# v1.net
KiCad netlist of a schematic drawn in EAGLE
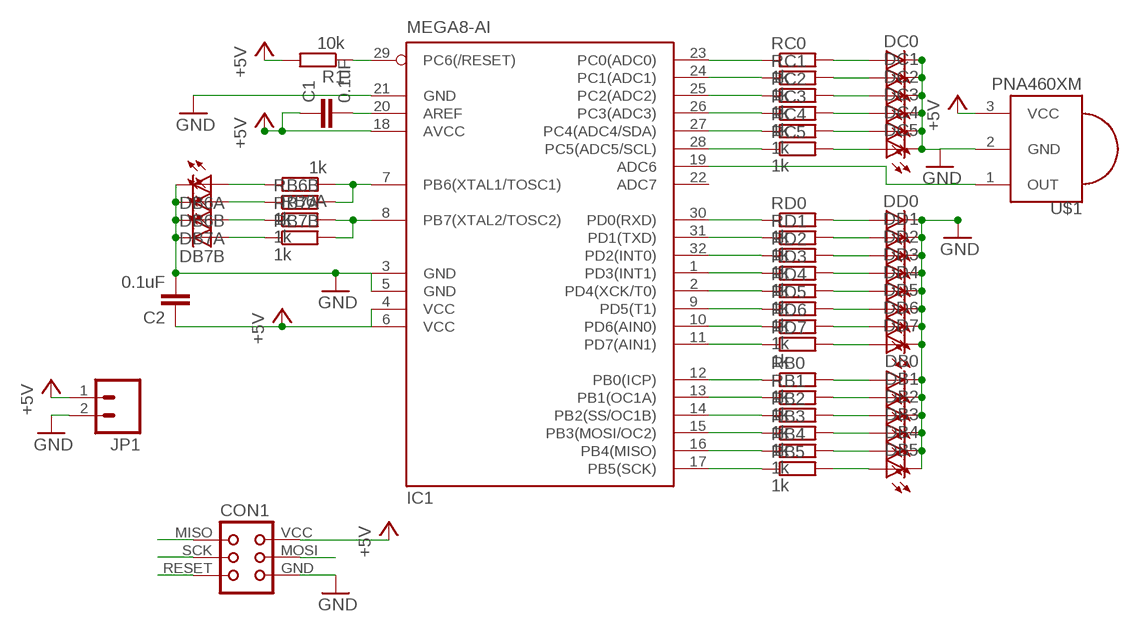
[diagram p0: schematic, sheet 1]

(export (version "E")
  (design (tool "Eeschema 10.0.6"))
  (components
    (comp (ref "C1")
      (value "0.1uF")
      (footprint "eagle-import:C1206")
      (libsource (lib "eagle-import") (part "C-EUC1206"))
    )
    (comp (ref "C2")
      (value "0.1uF")
      (footprint "eagle-import:C1206")
      (libsource (lib "eagle-import") (part "C-EUC1206"))
    )
    (comp (ref "CON1")
      (value "TINYISP")
      (footprint "eagle-import:TINYISP")
      (libsource (lib "eagle-import") (part "TINYISP"))
    )
    (comp (ref "DB0")
      (value "LED3MM")
      (footprint "eagle-import:LED3MM")
      (libsource (lib "eagle-import") (part "LED3MM"))
    )
    (comp (ref "DB1")
      (value "LED3MM")
      (footprint "eagle-import:LED3MM")
      (libsource (lib "eagle-import") (part "LED3MM"))
    )
    (comp (ref "DB2")
      (value "LED3MM")
      (footprint "eagle-import:LED3MM")
      (libsource (lib "eagle-import") (part "LED3MM"))
    )
    (comp (ref "DB3")
      (value "LED3MM")
      (footprint "eagle-import:LED3MM")
      (libsource (lib "eagle-import") (part "LED3MM"))
    )
    (comp (ref "DB4")
      (value "LED3MM")
      (footprint "eagle-import:LED3MM")
      (libsource (lib "eagle-import") (part "LED3MM"))
    )
    (comp (ref "DB5")
      (value "LED3MM")
      (footprint "eagle-import:LED3MM")
      (libsource (lib "eagle-import") (part "LED3MM"))
    )
    (comp (ref "DB6A")
      (value "LED3MM")
      (footprint "eagle-import:LED3MM")
      (libsource (lib "eagle-import") (part "LED3MM"))
    )
    (comp (ref "DB6B")
      (value "LED3MM")
      (footprint "eagle-import:LED3MM")
      (libsource (lib "eagle-import") (part "LED3MM"))
    )
    (comp (ref "DB7A")
      (value "LED3MM")
      (footprint "eagle-import:LED3MM")
      (libsource (lib "eagle-import") (part "LED3MM"))
    )
    (comp (ref "DB7B")
      (value "LED3MM")
      (footprint "eagle-import:LED3MM")
      (libsource (lib "eagle-import") (part "LED3MM"))
    )
    (comp (ref "DC0")
      (value "LED3MM")
      (footprint "eagle-import:LED3MM")
      (libsource (lib "eagle-import") (part "LED3MM"))
    )
    (comp (ref "DC1")
      (value "LED3MM")
      (footprint "eagle-import:LED3MM")
      (libsource (lib "eagle-import") (part "LED3MM"))
    )
    (comp (ref "DC2")
      (value "LED3MM")
      (footprint "eagle-import:LED3MM")
      (libsource (lib "eagle-import") (part "LED3MM"))
    )
    (comp (ref "DC3")
      (value "LED3MM")
      (footprint "eagle-import:LED3MM")
      (libsource (lib "eagle-import") (part "LED3MM"))
    )
    (comp (ref "DC4")
      (value "LED3MM")
      (footprint "eagle-import:LED3MM")
      (libsource (lib "eagle-import") (part "LED3MM"))
    )
    (comp (ref "DC5")
      (value "LED3MM")
      (footprint "eagle-import:LED3MM")
      (libsource (lib "eagle-import") (part "LED3MM"))
    )
    (comp (ref "DD0")
      (value "LED3MM")
      (footprint "eagle-import:LED3MM")
      (libsource (lib "eagle-import") (part "LED3MM"))
    )
    (comp (ref "DD1")
      (value "LED3MM")
      (footprint "eagle-import:LED3MM")
      (libsource (lib "eagle-import") (part "LED3MM"))
    )
    (comp (ref "DD2")
      (value "LED3MM")
      (footprint "eagle-import:LED3MM")
      (libsource (lib "eagle-import") (part "LED3MM"))
    )
    (comp (ref "DD3")
      (value "LED3MM")
      (footprint "eagle-import:LED3MM")
      (libsource (lib "eagle-import") (part "LED3MM"))
    )
    (comp (ref "DD4")
      (value "LED3MM")
      (footprint "eagle-import:LED3MM")
      (libsource (lib "eagle-import") (part "LED3MM"))
    )
    (comp (ref "DD5")
      (value "LED3MM")
      (footprint "eagle-import:LED3MM")
      (libsource (lib "eagle-import") (part "LED3MM"))
    )
    (comp (ref "DD6")
      (value "LED3MM")
      (footprint "eagle-import:LED3MM")
      (libsource (lib "eagle-import") (part "LED3MM"))
    )
    (comp (ref "DD7")
      (value "LED3MM")
      (footprint "eagle-import:LED3MM")
      (libsource (lib "eagle-import") (part "LED3MM"))
    )
    (comp (ref "IC1")
      (value "MEGA8-AI")
      (footprint "eagle-import:TQFP32-08")
      (fields (field (name "MPN") "ATMEGA8-16AU"))
      (libsource (lib "eagle-import") (part "MEGA8-AI"))
    )
    (comp (ref "JP1")
      (value "M023.5MM")
      (footprint "eagle-import:SCREWTERMINAL-3.5MM-2")
      (libsource (lib "eagle-import") (part "M023.5MM"))
    )
    (comp (ref "R1")
      (value "10k")
      (footprint "eagle-import:M1206")
      (libsource (lib "eagle-import") (part "R-EU_M1206"))
    )
    (comp (ref "RB0")
      (value "1k")
      (footprint "eagle-import:M1206")
      (libsource (lib "eagle-import") (part "R-EU_M1206"))
    )
    (comp (ref "RB1")
      (value "1k")
      (footprint "eagle-import:M1206")
      (libsource (lib "eagle-import") (part "R-EU_M1206"))
    )
    (comp (ref "RB2")
      (value "1k")
      (footprint "eagle-import:M1206")
      (libsource (lib "eagle-import") (part "R-EU_M1206"))
    )
    (comp (ref "RB3")
      (value "1k")
      (footprint "eagle-import:M1206")
      (libsource (lib "eagle-import") (part "R-EU_M1206"))
    )
    (comp (ref "RB4")
      (value "1k")
      (footprint "eagle-import:M1206")
      (libsource (lib "eagle-import") (part "R-EU_M1206"))
    )
    (comp (ref "RB5")
      (value "1k")
      (footprint "eagle-import:M1206")
      (libsource (lib "eagle-import") (part "R-EU_M1206"))
    )
    (comp (ref "RB6A")
      (value "1k")
      (footprint "eagle-import:M1206")
      (libsource (lib "eagle-import") (part "R-EU_M1206"))
    )
    (comp (ref "RB6B")
      (value "1k")
      (footprint "eagle-import:M1206")
      (libsource (lib "eagle-import") (part "R-EU_M1206"))
    )
    (comp (ref "RB7A")
      (value "1k")
      (footprint "eagle-import:M1206")
      (libsource (lib "eagle-import") (part "R-EU_M1206"))
    )
    (comp (ref "RB7B")
      (value "1k")
      (footprint "eagle-import:M1206")
      (libsource (lib "eagle-import") (part "R-EU_M1206"))
    )
    (comp (ref "RC0")
      (value "1k")
      (footprint "eagle-import:M1206")
      (libsource (lib "eagle-import") (part "R-EU_M1206"))
    )
    (comp (ref "RC1")
      (value "1k")
      (footprint "eagle-import:M1206")
      (libsource (lib "eagle-import") (part "R-EU_M1206"))
    )
    (comp (ref "RC2")
      (value "1k")
      (footprint "eagle-import:M1206")
      (libsource (lib "eagle-import") (part "R-EU_M1206"))
    )
    (comp (ref "RC3")
      (value "1k")
      (footprint "eagle-import:M1206")
      (libsource (lib "eagle-import") (part "R-EU_M1206"))
    )
    (comp (ref "RC4")
      (value "1k")
      (footprint "eagle-import:M1206")
      (libsource (lib "eagle-import") (part "R-EU_M1206"))
    )
    (comp (ref "RC5")
      (value "1k")
      (footprint "eagle-import:M1206")
      (libsource (lib "eagle-import") (part "R-EU_M1206"))
    )
    (comp (ref "RD0")
      (value "1k")
      (footprint "eagle-import:M1206")
      (libsource (lib "eagle-import") (part "R-EU_M1206"))
    )
    (comp (ref "RD1")
      (value "1k")
      (footprint "eagle-import:M1206")
      (libsource (lib "eagle-import") (part "R-EU_M1206"))
    )
    (comp (ref "RD2")
      (value "1k")
      (footprint "eagle-import:M1206")
      (libsource (lib "eagle-import") (part "R-EU_M1206"))
    )
    (comp (ref "RD3")
      (value "1k")
      (footprint "eagle-import:M1206")
      (libsource (lib "eagle-import") (part "R-EU_M1206"))
    )
    (comp (ref "RD4")
      (value "1k")
      (footprint "eagle-import:M1206")
      (libsource (lib "eagle-import") (part "R-EU_M1206"))
    )
    (comp (ref "RD5")
      (value "1k")
      (footprint "eagle-import:M1206")
      (libsource (lib "eagle-import") (part "R-EU_M1206"))
    )
    (comp (ref "RD6")
      (value "1k")
      (footprint "eagle-import:M1206")
      (libsource (lib "eagle-import") (part "R-EU_M1206"))
    )
    (comp (ref "RD7")
      (value "1k")
      (footprint "eagle-import:M1206")
      (libsource (lib "eagle-import") (part "R-EU_M1206"))
    )
    (comp (ref "U$1")
      (value "PNA460XM")
      (footprint "eagle-import:PNA460XM")
      (libsource (lib "eagle-import") (part "PNA460XM"))
    )
  )
  (nets
    (net (code "1") (name "+5V") (class "Default")
      (node (ref "C1") (pin "1") (pinfunction "1_1") (pintype "passive"))
      (node (ref "C2") (pin "1") (pinfunction "1_1") (pintype "passive"))
      (node (ref "CON1") (pin "VCC") (pinfunction "VCC_VCC") (pintype "passive"))
      (node (ref "IC1") (pin "18") (pinfunction "AVCC_18") (pintype "power_in"))
      (node (ref "IC1") (pin "4") (pinfunction "VCC_4") (pintype "power_in"))
      (node (ref "IC1") (pin "6") (pinfunction "VCC_6") (pintype "power_in"))
      (node (ref "JP1") (pin "1") (pinfunction "1_1") (pintype "passive"))
      (node (ref "R1") (pin "2") (pinfunction "2_2") (pintype "passive"))
      (node (ref "U$1") (pin "3") (pinfunction "VCC_3") (pintype "power_in"))
    )
    (net (code "2") (name "/MISO") (class "Default")
      (node (ref "CON1") (pin "MISO") (pinfunction "MISO_MISO") (pintype "passive"))
      (node (ref "IC1") (pin "16") (pinfunction "PB4(MISO)_16") (pintype "bidirectional"))
      (node (ref "RB4") (pin "1") (pinfunction "1_1") (pintype "passive"))
    )
    (net (code "3") (name "/MOSI") (class "Default")
      (node (ref "CON1") (pin "MOSI") (pinfunction "MOSI_MOSI") (pintype "passive"))
      (node (ref "IC1") (pin "15") (pinfunction "PB3(MOSI/OC2)_15") (pintype "bidirectional"))
      (node (ref "RB3") (pin "1") (pinfunction "1_1") (pintype "passive"))
    )
    (net (code "4") (name "/RESET") (class "Default")
      (node (ref "CON1") (pin "RESET") (pinfunction "RESET_RESET") (pintype "passive"))
      (node (ref "IC1") (pin "29") (pinfunction "PC6(/RESET)_29") (pintype "bidirectional"))
      (node (ref "R1") (pin "1") (pinfunction "1_1") (pintype "passive"))
    )
    (net (code "5") (name "/SCK") (class "Default")
      (node (ref "CON1") (pin "SCK") (pinfunction "SCK_SCK") (pintype "passive"))
      (node (ref "IC1") (pin "17") (pinfunction "PB5(SCK)_17") (pintype "bidirectional"))
      (node (ref "RB5") (pin "1") (pinfunction "1_1") (pintype "passive"))
    )
    (net (code "6") (name "GND") (class "Default")
      (node (ref "C2") (pin "2") (pinfunction "2_2") (pintype "passive"))
      (node (ref "CON1") (pin "GND") (pinfunction "GND_GND") (pintype "passive"))
      (node (ref "DB0") (pin "K") (pinfunction "C_K") (pintype "passive"))
      (node (ref "DB1") (pin "K") (pinfunction "C_K") (pintype "passive"))
      (node (ref "DB2") (pin "K") (pinfunction "C_K") (pintype "passive"))
      (node (ref "DB3") (pin "K") (pinfunction "C_K") (pintype "passive"))
      (node (ref "DB4") (pin "K") (pinfunction "C_K") (pintype "passive"))
      (node (ref "DB5") (pin "K") (pinfunction "C_K") (pintype "passive"))
      (node (ref "DB6A") (pin "K") (pinfunction "C_K") (pintype "passive"))
      (node (ref "DB6B") (pin "K") (pinfunction "C_K") (pintype "passive"))
      (node (ref "DB7A") (pin "K") (pinfunction "C_K") (pintype "passive"))
      (node (ref "DB7B") (pin "K") (pinfunction "C_K") (pintype "passive"))
      (node (ref "DC0") (pin "K") (pinfunction "C_K") (pintype "passive"))
      (node (ref "DC1") (pin "K") (pinfunction "C_K") (pintype "passive"))
      (node (ref "DC2") (pin "K") (pinfunction "C_K") (pintype "passive"))
      (node (ref "DC3") (pin "K") (pinfunction "C_K") (pintype "passive"))
      (node (ref "DC4") (pin "K") (pinfunction "C_K") (pintype "passive"))
      (node (ref "DC5") (pin "K") (pinfunction "C_K") (pintype "passive"))
      (node (ref "DD0") (pin "K") (pinfunction "C_K") (pintype "passive"))
      (node (ref "DD1") (pin "K") (pinfunction "C_K") (pintype "passive"))
      (node (ref "DD2") (pin "K") (pinfunction "C_K") (pintype "passive"))
      (node (ref "DD3") (pin "K") (pinfunction "C_K") (pintype "passive"))
      (node (ref "DD4") (pin "K") (pinfunction "C_K") (pintype "passive"))
      (node (ref "DD5") (pin "K") (pinfunction "C_K") (pintype "passive"))
      (node (ref "DD6") (pin "K") (pinfunction "C_K") (pintype "passive"))
      (node (ref "DD7") (pin "K") (pinfunction "C_K") (pintype "passive"))
      (node (ref "IC1") (pin "21") (pinfunction "GND_21") (pintype "power_in"))
      (node (ref "IC1") (pin "3") (pinfunction "GND_3") (pintype "power_in"))
      (node (ref "IC1") (pin "5") (pinfunction "GND_5") (pintype "power_in"))
      (node (ref "JP1") (pin "2") (pinfunction "2_2") (pintype "passive"))
      (node (ref "U$1") (pin "2") (pinfunction "GND_2") (pintype "power_in"))
    )
    (net (code "7") (name "Net-(DB0-PadA)") (class "Default")
      (node (ref "DB0") (pin "A") (pinfunction "A_A") (pintype "passive"))
      (node (ref "RB0") (pin "2") (pinfunction "2_2") (pintype "passive"))
    )
    (net (code "8") (name "Net-(DB1-PadA)") (class "Default")
      (node (ref "DB1") (pin "A") (pinfunction "A_A") (pintype "passive"))
      (node (ref "RB1") (pin "2") (pinfunction "2_2") (pintype "passive"))
    )
    (net (code "9") (name "Net-(DB2-PadA)") (class "Default")
      (node (ref "DB2") (pin "A") (pinfunction "A_A") (pintype "passive"))
      (node (ref "RB2") (pin "2") (pinfunction "2_2") (pintype "passive"))
    )
    (net (code "10") (name "Net-(DB3-PadA)") (class "Default")
      (node (ref "DB3") (pin "A") (pinfunction "A_A") (pintype "passive"))
      (node (ref "RB3") (pin "2") (pinfunction "2_2") (pintype "passive"))
    )
    (net (code "11") (name "Net-(DB4-PadA)") (class "Default")
      (node (ref "DB4") (pin "A") (pinfunction "A_A") (pintype "passive"))
      (node (ref "RB4") (pin "2") (pinfunction "2_2") (pintype "passive"))
    )
    (net (code "12") (name "Net-(DB5-PadA)") (class "Default")
      (node (ref "DB5") (pin "A") (pinfunction "A_A") (pintype "passive"))
      (node (ref "RB5") (pin "2") (pinfunction "2_2") (pintype "passive"))
    )
    (net (code "13") (name "Net-(DB6A-PadA)") (class "Default")
      (node (ref "DB6A") (pin "A") (pinfunction "A_A") (pintype "passive"))
      (node (ref "RB6A") (pin "2") (pinfunction "2_2") (pintype "passive"))
    )
    (net (code "14") (name "Net-(DB6B-PadA)") (class "Default")
      (node (ref "DB6B") (pin "A") (pinfunction "A_A") (pintype "passive"))
      (node (ref "RB6B") (pin "1") (pinfunction "1_1") (pintype "passive"))
    )
    (net (code "15") (name "Net-(DB7A-PadA)") (class "Default")
      (node (ref "DB7A") (pin "A") (pinfunction "A_A") (pintype "passive"))
      (node (ref "RB7A") (pin "1") (pinfunction "1_1") (pintype "passive"))
    )
    (net (code "16") (name "Net-(DB7B-PadA)") (class "Default")
      (node (ref "DB7B") (pin "A") (pinfunction "A_A") (pintype "passive"))
      (node (ref "RB7B") (pin "1") (pinfunction "1_1") (pintype "passive"))
    )
    (net (code "17") (name "Net-(DC0-PadA)") (class "Default")
      (node (ref "DC0") (pin "A") (pinfunction "A_A") (pintype "passive"))
      (node (ref "RC0") (pin "2") (pinfunction "2_2") (pintype "passive"))
    )
    (net (code "18") (name "Net-(DC1-PadA)") (class "Default")
      (node (ref "DC1") (pin "A") (pinfunction "A_A") (pintype "passive"))
      (node (ref "RC1") (pin "2") (pinfunction "2_2") (pintype "passive"))
    )
    (net (code "19") (name "Net-(DC2-PadA)") (class "Default")
      (node (ref "DC2") (pin "A") (pinfunction "A_A") (pintype "passive"))
      (node (ref "RC2") (pin "2") (pinfunction "2_2") (pintype "passive"))
    )
    (net (code "20") (name "Net-(DC3-PadA)") (class "Default")
      (node (ref "DC3") (pin "A") (pinfunction "A_A") (pintype "passive"))
      (node (ref "RC3") (pin "2") (pinfunction "2_2") (pintype "passive"))
    )
    (net (code "21") (name "Net-(DC4-PadA)") (class "Default")
      (node (ref "DC4") (pin "A") (pinfunction "A_A") (pintype "passive"))
      (node (ref "RC4") (pin "2") (pinfunction "2_2") (pintype "passive"))
    )
    (net (code "22") (name "Net-(DC5-PadA)") (class "Default")
      (node (ref "DC5") (pin "A") (pinfunction "A_A") (pintype "passive"))
      (node (ref "RC5") (pin "2") (pinfunction "2_2") (pintype "passive"))
    )
    (net (code "23") (name "Net-(DD0-PadA)") (class "Default")
      (node (ref "DD0") (pin "A") (pinfunction "A_A") (pintype "passive"))
      (node (ref "RD0") (pin "2") (pinfunction "2_2") (pintype "passive"))
    )
    (net (code "24") (name "Net-(DD1-PadA)") (class "Default")
      (node (ref "DD1") (pin "A") (pinfunction "A_A") (pintype "passive"))
      (node (ref "RD1") (pin "2") (pinfunction "2_2") (pintype "passive"))
    )
    (net (code "25") (name "Net-(DD2-PadA)") (class "Default")
      (node (ref "DD2") (pin "A") (pinfunction "A_A") (pintype "passive"))
      (node (ref "RD2") (pin "2") (pinfunction "2_2") (pintype "passive"))
    )
    (net (code "26") (name "Net-(DD3-PadA)") (class "Default")
      (node (ref "DD3") (pin "A") (pinfunction "A_A") (pintype "passive"))
      (node (ref "RD3") (pin "2") (pinfunction "2_2") (pintype "passive"))
    )
    (net (code "27") (name "Net-(DD4-PadA)") (class "Default")
      (node (ref "DD4") (pin "A") (pinfunction "A_A") (pintype "passive"))
      (node (ref "RD4") (pin "2") (pinfunction "2_2") (pintype "passive"))
    )
    (net (code "28") (name "Net-(DD5-PadA)") (class "Default")
      (node (ref "DD5") (pin "A") (pinfunction "A_A") (pintype "passive"))
      (node (ref "RD5") (pin "2") (pinfunction "2_2") (pintype "passive"))
    )
    (net (code "29") (name "Net-(DD6-PadA)") (class "Default")
      (node (ref "DD6") (pin "A") (pinfunction "A_A") (pintype "passive"))
      (node (ref "RD6") (pin "2") (pinfunction "2_2") (pintype "passive"))
    )
    (net (code "30") (name "Net-(DD7-PadA)") (class "Default")
      (node (ref "DD7") (pin "A") (pinfunction "A_A") (pintype "passive"))
      (node (ref "RD7") (pin "2") (pinfunction "2_2") (pintype "passive"))
    )
    (net (code "31") (name "Net-(IC1-ADC6)") (class "Default")
      (node (ref "IC1") (pin "19") (pinfunction "ADC6_19") (pintype "bidirectional"))
      (node (ref "U$1") (pin "1") (pinfunction "OUT_1") (pintype "output"))
    )
    (net (code "32") (name "Net-(IC1-AREF)") (class "Default")
      (node (ref "C1") (pin "2") (pinfunction "2_2") (pintype "passive"))
      (node (ref "IC1") (pin "20") (pinfunction "AREF_20") (pintype "passive"))
    )
    (net (code "33") (name "Net-(IC1-PB0(ICP))") (class "Default")
      (node (ref "IC1") (pin "12") (pinfunction "PB0(ICP)_12") (pintype "bidirectional"))
      (node (ref "RB0") (pin "1") (pinfunction "1_1") (pintype "passive"))
    )
    (net (code "34") (name "Net-(IC1-PB1(OC1A))") (class "Default")
      (node (ref "IC1") (pin "13") (pinfunction "PB1(OC1A)_13") (pintype "bidirectional"))
      (node (ref "RB1") (pin "1") (pinfunction "1_1") (pintype "passive"))
    )
    (net (code "35") (name "Net-(IC1-PB2(SS{slash}OC1B))") (class "Default")
      (node (ref "IC1") (pin "14") (pinfunction "PB2(SS/OC1B)_14") (pintype "bidirectional"))
      (node (ref "RB2") (pin "1") (pinfunction "1_1") (pintype "passive"))
    )
    (net (code "36") (name "Net-(IC1-PB6(XTAL1{slash}TOSC1))") (class "Default")
      (node (ref "IC1") (pin "7") (pinfunction "PB6(XTAL1/TOSC1)_7") (pintype "bidirectional"))
      (node (ref "RB6A") (pin "1") (pinfunction "1_1") (pintype "passive"))
      (node (ref "RB6B") (pin "2") (pinfunction "2_2") (pintype "passive"))
    )
    (net (code "37") (name "Net-(IC1-PB7(XTAL2{slash}TOSC2))") (class "Default")
      (node (ref "IC1") (pin "8") (pinfunction "PB7(XTAL2/TOSC2)_8") (pintype "bidirectional"))
      (node (ref "RB7A") (pin "2") (pinfunction "2_2") (pintype "passive"))
      (node (ref "RB7B") (pin "2") (pinfunction "2_2") (pintype "passive"))
    )
    (net (code "38") (name "Net-(IC1-PC0(ADC0))") (class "Default")
      (node (ref "IC1") (pin "23") (pinfunction "PC0(ADC0)_23") (pintype "bidirectional"))
      (node (ref "RC0") (pin "1") (pinfunction "1_1") (pintype "passive"))
    )
    (net (code "39") (name "Net-(IC1-PC1(ADC1))") (class "Default")
      (node (ref "IC1") (pin "24") (pinfunction "PC1(ADC1)_24") (pintype "bidirectional"))
      (node (ref "RC1") (pin "1") (pinfunction "1_1") (pintype "passive"))
    )
    (net (code "40") (name "Net-(IC1-PC2(ADC2))") (class "Default")
      (node (ref "IC1") (pin "25") (pinfunction "PC2(ADC2)_25") (pintype "bidirectional"))
      (node (ref "RC2") (pin "1") (pinfunction "1_1") (pintype "passive"))
    )
    (net (code "41") (name "Net-(IC1-PC3(ADC3))") (class "Default")
      (node (ref "IC1") (pin "26") (pinfunction "PC3(ADC3)_26") (pintype "bidirectional"))
      (node (ref "RC3") (pin "1") (pinfunction "1_1") (pintype "passive"))
    )
    (net (code "42") (name "Net-(IC1-PC4(ADC4{slash}SDA))") (class "Default")
      (node (ref "IC1") (pin "27") (pinfunction "PC4(ADC4/SDA)_27") (pintype "bidirectional"))
      (node (ref "RC4") (pin "1") (pinfunction "1_1") (pintype "passive"))
    )
    (net (code "43") (name "Net-(IC1-PC5(ADC5{slash}SCL))") (class "Default")
      (node (ref "IC1") (pin "28") (pinfunction "PC5(ADC5/SCL)_28") (pintype "bidirectional"))
      (node (ref "RC5") (pin "1") (pinfunction "1_1") (pintype "passive"))
    )
    (net (code "44") (name "Net-(IC1-PD0(RXD))") (class "Default")
      (node (ref "IC1") (pin "30") (pinfunction "PD0(RXD)_30") (pintype "bidirectional"))
      (node (ref "RD0") (pin "1") (pinfunction "1_1") (pintype "passive"))
    )
    (net (code "45") (name "Net-(IC1-PD1(TXD))") (class "Default")
      (node (ref "IC1") (pin "31") (pinfunction "PD1(TXD)_31") (pintype "bidirectional"))
      (node (ref "RD1") (pin "1") (pinfunction "1_1") (pintype "passive"))
    )
    (net (code "46") (name "Net-(IC1-PD2(INT0))") (class "Default")
      (node (ref "IC1") (pin "32") (pinfunction "PD2(INT0)_32") (pintype "bidirectional"))
      (node (ref "RD2") (pin "1") (pinfunction "1_1") (pintype "passive"))
    )
    (net (code "47") (name "Net-(IC1-PD3(INT1))") (class "Default")
      (node (ref "IC1") (pin "1") (pinfunction "PD3(INT1)_1") (pintype "bidirectional"))
      (node (ref "RD3") (pin "1") (pinfunction "1_1") (pintype "passive"))
    )
    (net (code "48") (name "Net-(IC1-PD4(XCK{slash}T0))") (class "Default")
      (node (ref "IC1") (pin "2") (pinfunction "PD4(XCK/T0)_2") (pintype "bidirectional"))
      (node (ref "RD4") (pin "1") (pinfunction "1_1") (pintype "passive"))
    )
    (net (code "49") (name "Net-(IC1-PD5(T1))") (class "Default")
      (node (ref "IC1") (pin "9") (pinfunction "PD5(T1)_9") (pintype "bidirectional"))
      (node (ref "RD5") (pin "1") (pinfunction "1_1") (pintype "passive"))
    )
    (net (code "50") (name "Net-(IC1-PD6(AIN0))") (class "Default")
      (node (ref "IC1") (pin "10") (pinfunction "PD6(AIN0)_10") (pintype "bidirectional"))
      (node (ref "RD6") (pin "1") (pinfunction "1_1") (pintype "passive"))
    )
    (net (code "51") (name "Net-(IC1-PD7(AIN1))") (class "Default")
      (node (ref "IC1") (pin "11") (pinfunction "PD7(AIN1)_11") (pintype "bidirectional"))
      (node (ref "RD7") (pin "1") (pinfunction "1_1") (pintype "passive"))
    )
    (net (code "52") (name "unconnected-(IC1-ADC7-Pad22)") (class "Default")
      (node (ref "IC1") (pin "22") (pinfunction "ADC7_22") (pintype "bidirectional"))
    )
  )
)
